# DXP.net
KiCad netlist of a schematic drawn in Altium Designer
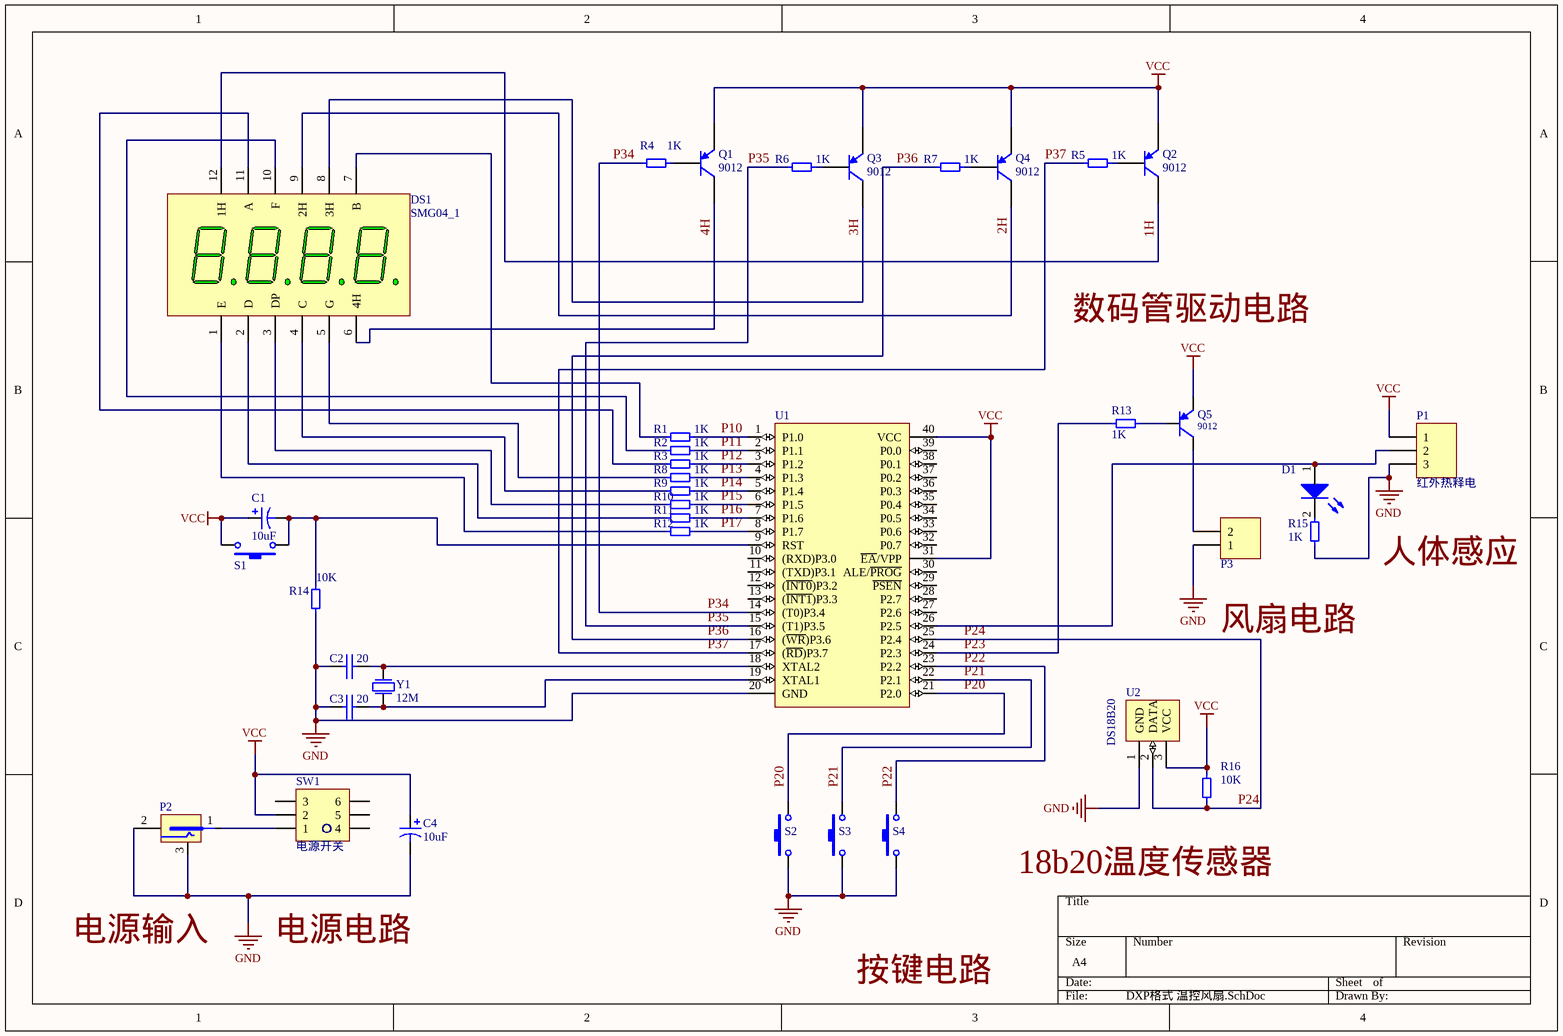
[diagram p0: DXP格式 温控风扇.SchDoc]

(export (version "E")
  (design (tool "Eeschema 10.0.6"))
  (components
    (comp (ref "C1")
      (value "10uF")
      (footprint "C_10")
      (description "Polarized Capacitor (Radial)")
      (fields (field (name "PUBLISHER") "Altium Limited"))
      (libsource (lib "简易动环监控系统") (part "Cap Pol1"))
    )
    (comp (ref "C2")
      (value "20")
      (footprint "CAP CP")
      (description "电容")
      (libsource (lib "C8051F020最小2") (part "CAP"))
    )
    (comp (ref "C3")
      (value "20")
      (footprint "CAP CP")
      (description "电容")
      (libsource (lib "C8051F020最小2") (part "CAP"))
    )
    (comp (ref "C4")
      (value "10uF")
      (footprint "C_10")
      (description "Polarized Capacitor (Radial)")
      (fields (field (name "PUBLISHER") "Altium Limited"))
      (libsource (lib "简易动环监控系统") (part "Cap Pol1"))
    )
    (comp (ref "D1") (value "~") (footprint "LED直插") (libsource (lib "实用原理图库") (part "D")))
    (comp (ref "DS1") (value "SMG04_1") (footprint "SMG04") (libsource (lib "我自己的") (part "SMG04_1")))
    (comp (ref "P1")
      (value "红外热释电")
      (footprint "HDR1X3")
      (description "Header, 3-Pin")
      (fields (field (name "PUBLISHER") "Altium Limited"))
      (libsource (lib "Miscellaneous Connectors") (part "MHDR1X3"))
    )
    (comp (ref "P2") (value "电源输入") (footprint "DC2.1") (libsource (lib "我自己的") (part "POWER")))
    (comp (ref "P3")
      (value "Header 2")
      (footprint "POWER -  小电源座")
      (description "Header, 2-Pin")
      (fields (field (name "PUBLISHER") "Altium Limited"))
      (libsource (lib "Miscellaneous Connectors") (part "Header 2"))
    )
    (comp (ref "Q1")
      (value "9012")
      (footprint "s三极管直插")
      (description "PNP General Purpose Amplifier")
      (fields (field (name "PUBLISHER") "Altium Limited"))
      (libsource (lib "Miscellaneous Devices") (part "2N3906"))
    )
    (comp (ref "Q2")
      (value "9012")
      (footprint "s三极管直插")
      (description "PNP General Purpose Amplifier")
      (fields (field (name "PUBLISHER") "Altium Limited"))
      (libsource (lib "Miscellaneous Devices") (part "2N3906"))
    )
    (comp (ref "Q3")
      (value "9012")
      (footprint "s三极管直插")
      (description "PNP General Purpose Amplifier")
      (fields (field (name "PUBLISHER") "Altium Limited"))
      (libsource (lib "Miscellaneous Devices") (part "2N3906"))
    )
    (comp (ref "Q4")
      (value "9012")
      (footprint "s三极管直插")
      (description "PNP General Purpose Amplifier")
      (fields (field (name "PUBLISHER") "Altium Limited"))
      (libsource (lib "Miscellaneous Devices") (part "2N3906"))
    )
    (comp (ref "Q5")
      (value "9012")
      (footprint "s三极管直插")
      (description "PNP General Purpose Amplifier")
      (fields (field (name "PUBLISHER") "Altium Limited"))
      (libsource (lib "实验板原理图") (part "2N3906"))
    )
    (comp (ref "R1") (value "1K") (footprint "AXIAL0.3") (libsource (lib "C8051F020最小2") (part "RES2")))
    (comp (ref "R2") (value "1K") (footprint "AXIAL0.3") (libsource (lib "C8051F020最小2") (part "RES2")))
    (comp (ref "R3") (value "1K") (footprint "AXIAL0.3") (libsource (lib "C8051F020最小2") (part "RES2")))
    (comp (ref "R4") (value "1K") (footprint "AXIAL0.3") (libsource (lib "C8051F020最小2") (part "RES2")))
    (comp (ref "R5") (value "1K") (footprint "AXIAL0.3") (libsource (lib "C8051F020最小2") (part "RES2")))
    (comp (ref "R6") (value "1K") (footprint "AXIAL0.3") (libsource (lib "C8051F020最小2") (part "RES2")))
    (comp (ref "R7") (value "1K") (footprint "AXIAL0.3") (libsource (lib "C8051F020最小2") (part "RES2")))
    (comp (ref "R8") (value "1K") (footprint "AXIAL0.3") (libsource (lib "C8051F020最小2") (part "RES2")))
    (comp (ref "R9") (value "1K") (footprint "AXIAL0.3") (libsource (lib "C8051F020最小2") (part "RES2")))
    (comp (ref "R10") (value "1K") (footprint "AXIAL0.3") (libsource (lib "C8051F020最小2") (part "RES2")))
    (comp (ref "R11") (value "1K") (footprint "AXIAL0.3") (libsource (lib "C8051F020最小2") (part "RES2")))
    (comp (ref "R12") (value "1K") (footprint "AXIAL0.3") (libsource (lib "C8051F020最小2") (part "RES2")))
    (comp (ref "R13") (value "1K") (footprint "res400mil") (libsource (lib "C8051F020最小2") (part "RES2")))
    (comp (ref "R14") (value "10K") (footprint "AXIAL0.3") (libsource (lib "C8051F020最小2") (part "RES2")))
    (comp (ref "R15") (value "1K") (footprint "AXIAL0.3") (libsource (lib "C8051F020最小2") (part "RES2")))
    (comp (ref "R16") (value "10K") (footprint "AXIAL0.3") (libsource (lib "C8051F020最小2") (part "RES2")))
    (comp (ref "S1")
      (value "SW-PB")
      (footprint "key")
      (description "Switch")
      (fields (field (name "PUBLISHER") "Altium Limited"))
      (libsource (lib "实验板原理图") (part "SW-PB"))
    )
    (comp (ref "S2")
      (value "SW-PB")
      (footprint "key")
      (description "Switch")
      (fields (field (name "PUBLISHER") "Altium Limited"))
      (libsource (lib "实验板原理图") (part "SW-PB"))
    )
    (comp (ref "S3")
      (value "SW-PB")
      (footprint "key")
      (description "Switch")
      (fields (field (name "PUBLISHER") "Altium Limited"))
      (libsource (lib "实验板原理图") (part "SW-PB"))
    )
    (comp (ref "S4")
      (value "SW-PB")
      (footprint "key")
      (description "Switch")
      (fields (field (name "PUBLISHER") "Altium Limited"))
      (libsource (lib "实验板原理图") (part "SW-PB"))
    )
    (comp (ref "SW1") (value "电源开关") (footprint "sw_自锁 1") (libsource (lib "我自己的") (part "SW1")))
    (comp (ref "U1") (value "STC89C52") (footprint "DIP40 - 做板") (libsource (lib "实验板原理图") (part "U1")))
    (comp (ref "U2") (value "DS18B20") (footprint "DS18B20") (libsource (lib "实验板原理图") (part "DS18B20")))
    (comp (ref "Y1")
      (value "12M")
      (footprint "XTAL")
      (description "Crystal Oscillator")
      (libsource (lib "C8051F020最小2") (part "16M"))
    )
  )
  (nets
    (net (code "1") (name "/1H") (class "Default")
      (node (ref "DS1") (pin "12") (pinfunction "1H_12") (pintype "passive"))
      (node (ref "Q2") (pin "3") (pinfunction "C_3") (pintype "passive"))
    )
    (net (code "2") (name "/2H") (class "Default")
      (node (ref "DS1") (pin "9") (pinfunction "2H_9") (pintype "passive"))
      (node (ref "Q4") (pin "3") (pinfunction "C_3") (pintype "passive"))
    )
    (net (code "3") (name "/3H") (class "Default")
      (node (ref "DS1") (pin "8") (pinfunction "3H_8") (pintype "passive"))
      (node (ref "Q3") (pin "3") (pinfunction "C_3") (pintype "passive"))
    )
    (net (code "4") (name "/4H") (class "Default")
      (node (ref "DS1") (pin "6") (pinfunction "4H_6") (pintype "passive"))
      (node (ref "Q1") (pin "3") (pinfunction "C_3") (pintype "passive"))
    )
    (net (code "6") (name "/P10") (class "Default")
      (node (ref "R1") (pin "1") (pinfunction "1_1") (pintype "passive"))
      (node (ref "U1") (pin "1") (pinfunction "P1.0_1") (pintype "bidirectional"))
    )
    (net (code "7") (name "/P11") (class "Default")
      (node (ref "R2") (pin "1") (pinfunction "1_1") (pintype "passive"))
      (node (ref "U1") (pin "2") (pinfunction "P1.1_2") (pintype "bidirectional"))
    )
    (net (code "8") (name "/P12") (class "Default")
      (node (ref "R3") (pin "1") (pinfunction "1_1") (pintype "passive"))
      (node (ref "U1") (pin "3") (pinfunction "P1.2_3") (pintype "bidirectional"))
    )
    (net (code "9") (name "/P13") (class "Default")
      (node (ref "R8") (pin "1") (pinfunction "1_1") (pintype "passive"))
      (node (ref "U1") (pin "4") (pinfunction "P1.3_4") (pintype "bidirectional"))
    )
    (net (code "10") (name "/P14") (class "Default")
      (node (ref "R9") (pin "1") (pinfunction "1_1") (pintype "passive"))
      (node (ref "U1") (pin "5") (pinfunction "P1.4_5") (pintype "bidirectional"))
    )
    (net (code "11") (name "/P15") (class "Default")
      (node (ref "R10") (pin "1") (pinfunction "1_1") (pintype "passive"))
      (node (ref "U1") (pin "6") (pinfunction "P1.5_6") (pintype "bidirectional"))
    )
    (net (code "12") (name "/P16") (class "Default")
      (node (ref "R11") (pin "1") (pinfunction "1_1") (pintype "passive"))
      (node (ref "U1") (pin "7") (pinfunction "P1.6_7") (pintype "bidirectional"))
    )
    (net (code "13") (name "/P17") (class "Default")
      (node (ref "R12") (pin "1") (pinfunction "1_1") (pintype "passive"))
      (node (ref "U1") (pin "8") (pinfunction "P1.7_8") (pintype "bidirectional"))
    )
    (net (code "14") (name "/P20") (class "Default")
      (node (ref "S2") (pin "2") (pinfunction "2_2") (pintype "passive"))
      (node (ref "U1") (pin "21") (pinfunction "P2.0_21") (pintype "bidirectional"))
    )
    (net (code "15") (name "/P21") (class "Default")
      (node (ref "S3") (pin "2") (pinfunction "2_2") (pintype "passive"))
      (node (ref "U1") (pin "22") (pinfunction "P2.1_22") (pintype "bidirectional"))
    )
    (net (code "16") (name "/P22") (class "Default")
      (node (ref "S4") (pin "2") (pinfunction "2_2") (pintype "passive"))
      (node (ref "U1") (pin "23") (pinfunction "P2.2_23") (pintype "bidirectional"))
    )
    (net (code "17") (name "/P23") (class "Default")
      (node (ref "R13") (pin "1") (pinfunction "1_1") (pintype "passive"))
      (node (ref "U1") (pin "24") (pinfunction "P2.3_24") (pintype "bidirectional"))
    )
    (net (code "18") (name "/P24") (class "Default")
      (node (ref "R16") (pin "1") (pinfunction "1_1") (pintype "passive"))
      (node (ref "U1") (pin "25") (pinfunction "P2.4_25") (pintype "bidirectional"))
      (node (ref "U2") (pin "2") (pinfunction "DATA_2") (pintype "bidirectional"))
    )
    (net (code "19") (name "/P34") (class "Default")
      (node (ref "R4") (pin "2") (pinfunction "2_2") (pintype "passive"))
      (node (ref "U1") (pin "14") (pinfunction "(T0)P3.4_14") (pintype "bidirectional"))
    )
    (net (code "20") (name "/P35") (class "Default")
      (node (ref "R6") (pin "2") (pinfunction "2_2") (pintype "passive"))
      (node (ref "U1") (pin "15") (pinfunction "(T1)P3.5_15") (pintype "bidirectional"))
    )
    (net (code "21") (name "/P36") (class "Default")
      (node (ref "R7") (pin "2") (pinfunction "2_2") (pintype "passive"))
      (node (ref "U1") (pin "16") (pinfunction "(~{WR})P3.6_16") (pintype "bidirectional"))
    )
    (net (code "22") (name "/P37") (class "Default")
      (node (ref "R5") (pin "2") (pinfunction "2_2") (pintype "passive"))
      (node (ref "U1") (pin "17") (pinfunction "(~{RD})P3.7_17") (pintype "bidirectional"))
    )
    (net (code "28") (name "GND") (class "Default")
      (node (ref "C2") (pin "1") (pinfunction "1_1") (pintype "passive"))
      (node (ref "C3") (pin "1") (pinfunction "1_1") (pintype "passive"))
      (node (ref "C4") (pin "2") (pinfunction "2_2") (pintype "passive"))
      (node (ref "P1") (pin "3") (pinfunction "3_3") (pintype "passive"))
      (node (ref "P2") (pin "2") (pintype "passive"))
      (node (ref "P2") (pin "3") (pintype "passive"))
      (node (ref "P3") (pin "1") (pinfunction "1_1") (pintype "passive"))
      (node (ref "R14") (pin "1") (pinfunction "1_1") (pintype "passive"))
      (node (ref "R15") (pin "1") (pinfunction "1_1") (pintype "passive"))
      (node (ref "S2") (pin "1") (pinfunction "1_1") (pintype "passive"))
      (node (ref "S3") (pin "1") (pinfunction "1_1") (pintype "passive"))
      (node (ref "S4") (pin "1") (pinfunction "1_1") (pintype "passive"))
      (node (ref "U1") (pin "20") (pinfunction "GND_20") (pintype "power_in"))
      (node (ref "U2") (pin "1") (pinfunction "GND_1") (pintype "power_in"))
    )
    (net (code "29") (name "Net-(D1-Pad2)") (class "Default")
      (node (ref "D1") (pin "2") (pintype "passive"))
      (node (ref "R15") (pin "2") (pinfunction "2_2") (pintype "passive"))
    )
    (net (code "30") (name "Net-(DS1-A)") (class "Default")
      (node (ref "DS1") (pin "11") (pinfunction "A_11") (pintype "passive"))
      (node (ref "R3") (pin "2") (pinfunction "2_2") (pintype "passive"))
    )
    (net (code "31") (name "Net-(DS1-B)") (class "Default")
      (node (ref "DS1") (pin "7") (pinfunction "B_7") (pintype "passive"))
      (node (ref "R1") (pin "2") (pinfunction "2_2") (pintype "passive"))
    )
    (net (code "32") (name "Net-(DS1-C)") (class "Default")
      (node (ref "DS1") (pin "4") (pinfunction "C_4") (pintype "passive"))
      (node (ref "R9") (pin "2") (pinfunction "2_2") (pintype "passive"))
    )
    (net (code "33") (name "Net-(DS1-D)") (class "Default")
      (node (ref "DS1") (pin "2") (pinfunction "D_2") (pintype "passive"))
      (node (ref "R11") (pin "2") (pinfunction "2_2") (pintype "passive"))
    )
    (net (code "34") (name "Net-(DS1-DP)") (class "Default")
      (node (ref "DS1") (pin "3") (pinfunction "DP_3") (pintype "passive"))
      (node (ref "R10") (pin "2") (pinfunction "2_2") (pintype "passive"))
    )
    (net (code "35") (name "Net-(DS1-E)") (class "Default")
      (node (ref "DS1") (pin "1") (pinfunction "E_1") (pintype "passive"))
      (node (ref "R12") (pin "2") (pinfunction "2_2") (pintype "passive"))
    )
    (net (code "36") (name "Net-(DS1-F)") (class "Default")
      (node (ref "DS1") (pin "10") (pinfunction "F_10") (pintype "passive"))
      (node (ref "R2") (pin "2") (pinfunction "2_2") (pintype "passive"))
    )
    (net (code "37") (name "Net-(DS1-G)") (class "Default")
      (node (ref "DS1") (pin "5") (pinfunction "G_5") (pintype "passive"))
      (node (ref "R8") (pin "2") (pinfunction "2_2") (pintype "passive"))
    )
    (net (code "38") (name "Net-(P2-Pad1)") (class "Default")
      (node (ref "P2") (pin "1") (pintype "passive"))
      (node (ref "SW1") (pin "1") (pinfunction "1_1") (pintype "passive"))
    )
    (net (code "39") (name "Net-(Q1-B)") (class "Default")
      (node (ref "Q1") (pin "2") (pinfunction "B_2") (pintype "passive"))
      (node (ref "R4") (pin "1") (pinfunction "1_1") (pintype "passive"))
    )
    (net (code "40") (name "Net-(Q2-B)") (class "Default")
      (node (ref "Q2") (pin "2") (pinfunction "B_2") (pintype "passive"))
      (node (ref "R5") (pin "1") (pinfunction "1_1") (pintype "passive"))
    )
    (net (code "41") (name "Net-(Q3-B)") (class "Default")
      (node (ref "Q3") (pin "2") (pinfunction "B_2") (pintype "passive"))
      (node (ref "R6") (pin "1") (pinfunction "1_1") (pintype "passive"))
    )
    (net (code "42") (name "Net-(Q4-B)") (class "Default")
      (node (ref "Q4") (pin "2") (pinfunction "B_2") (pintype "passive"))
      (node (ref "R7") (pin "1") (pinfunction "1_1") (pintype "passive"))
    )
    (net (code "43") (name "Net-(Q5-B)") (class "Default")
      (node (ref "Q5") (pin "2") (pinfunction "B_2") (pintype "passive"))
      (node (ref "R13") (pin "2") (pinfunction "2_2") (pintype "passive"))
    )
    (net (code "44") (name "Net-(Q5-C)") (class "Default")
      (node (ref "P3") (pin "2") (pinfunction "2_2") (pintype "passive"))
      (node (ref "Q5") (pin "3") (pinfunction "C_3") (pintype "passive"))
    )
    (net (code "45") (name "Net-(U1-P2.5)") (class "Default")
      (node (ref "D1") (pin "1") (pintype "passive"))
      (node (ref "P1") (pin "2") (pinfunction "2_2") (pintype "passive"))
      (node (ref "U1") (pin "26") (pinfunction "P2.5_26") (pintype "bidirectional"))
    )
    (net (code "46") (name "Net-(U1-RST)") (class "Default")
      (node (ref "C1") (pin "2") (pinfunction "2_2") (pintype "passive"))
      (node (ref "R14") (pin "2") (pinfunction "2_2") (pintype "passive"))
      (node (ref "S1") (pin "1") (pinfunction "1_1") (pintype "passive"))
      (node (ref "U1") (pin "9") (pinfunction "RST_9") (pintype "bidirectional"))
    )
    (net (code "47") (name "Net-(U1-XTAL1)") (class "Default")
      (node (ref "C3") (pin "2") (pinfunction "2_2") (pintype "passive"))
      (node (ref "U1") (pin "19") (pinfunction "XTAL1_19") (pintype "bidirectional"))
      (node (ref "Y1") (pin "2") (pinfunction "P2_2") (pintype "passive"))
    )
    (net (code "48") (name "Net-(U1-XTAL2)") (class "Default")
      (node (ref "C2") (pin "2") (pinfunction "2_2") (pintype "passive"))
      (node (ref "U1") (pin "18") (pinfunction "XTAL2_18") (pintype "bidirectional"))
      (node (ref "Y1") (pin "1") (pinfunction "P1_1") (pintype "passive"))
    )
    (net (code "49") (name "VCC") (class "Default")
      (node (ref "C1") (pin "1") (pinfunction "1_1") (pintype "passive"))
      (node (ref "C4") (pin "1") (pinfunction "1_1") (pintype "passive"))
      (node (ref "P1") (pin "1") (pinfunction "1_1") (pintype "passive"))
      (node (ref "Q1") (pin "1") (pinfunction "E_1") (pintype "passive"))
      (node (ref "Q2") (pin "1") (pinfunction "E_1") (pintype "passive"))
      (node (ref "Q3") (pin "1") (pinfunction "E_1") (pintype "passive"))
      (node (ref "Q4") (pin "1") (pinfunction "E_1") (pintype "passive"))
      (node (ref "Q5") (pin "1") (pinfunction "E_1") (pintype "passive"))
      (node (ref "R16") (pin "2") (pinfunction "2_2") (pintype "passive"))
      (node (ref "S1") (pin "2") (pinfunction "2_2") (pintype "passive"))
      (node (ref "SW1") (pin "2") (pinfunction "2_2") (pintype "passive"))
      (node (ref "U1") (pin "31") (pinfunction "~{EA}/VPP_31") (pintype "power_in"))
      (node (ref "U1") (pin "40") (pinfunction "VCC_40") (pintype "power_in"))
      (node (ref "U2") (pin "3") (pinfunction "VCC_3") (pintype "power_in"))
    )
    (net (code "50") (name "unconnected-(SW1-Pad3)") (class "Default")
      (node (ref "SW1") (pin "3") (pinfunction "3_3") (pintype "passive"))
    )
    (net (code "51") (name "unconnected-(SW1-Pad4)") (class "Default")
      (node (ref "SW1") (pin "4") (pinfunction "4_4") (pintype "passive"))
    )
    (net (code "52") (name "unconnected-(SW1-Pad5)") (class "Default")
      (node (ref "SW1") (pin "5") (pinfunction "5_5") (pintype "passive"))
    )
    (net (code "53") (name "unconnected-(SW1-Pad6)") (class "Default")
      (node (ref "SW1") (pin "6") (pinfunction "6_6") (pintype "passive"))
    )
    (net (code "54") (name "unconnected-(U1-(RXD)P3.0-Pad10)") (class "Default")
      (node (ref "U1") (pin "10") (pinfunction "(RXD)P3.0_10") (pintype "bidirectional"))
    )
    (net (code "55") (name "unconnected-(U1-(TXD)P3.1-Pad11)") (class "Default")
      (node (ref "U1") (pin "11") (pinfunction "(TXD)P3.1_11") (pintype "bidirectional"))
    )
    (net (code "56") (name "unconnected-(U1-(~{INT0})P3.2-Pad12)") (class "Default")
      (node (ref "U1") (pin "12") (pinfunction "(~{INT0})P3.2_12") (pintype "bidirectional"))
    )
    (net (code "57") (name "unconnected-(U1-(~{INT1})P3.3-Pad13)") (class "Default")
      (node (ref "U1") (pin "13") (pinfunction "(~{INT1})P3.3_13") (pintype "bidirectional"))
    )
    (net (code "58") (name "unconnected-(U1-ALE{slash}~{PROG}-Pad30)") (class "Default")
      (node (ref "U1") (pin "30") (pinfunction "ALE/~{PROG}_30") (pintype "bidirectional"))
    )
    (net (code "59") (name "unconnected-(U1-P0.0-Pad39)") (class "Default")
      (node (ref "U1") (pin "39") (pinfunction "P0.0_39") (pintype "bidirectional"))
    )
    (net (code "60") (name "unconnected-(U1-P0.1-Pad38)") (class "Default")
      (node (ref "U1") (pin "38") (pinfunction "P0.1_38") (pintype "bidirectional"))
    )
    (net (code "61") (name "unconnected-(U1-P0.2-Pad37)") (class "Default")
      (node (ref "U1") (pin "37") (pinfunction "P0.2_37") (pintype "bidirectional"))
    )
    (net (code "62") (name "unconnected-(U1-P0.3-Pad36)") (class "Default")
      (node (ref "U1") (pin "36") (pinfunction "P0.3_36") (pintype "bidirectional"))
    )
    (net (code "63") (name "unconnected-(U1-P0.4-Pad35)") (class "Default")
      (node (ref "U1") (pin "35") (pinfunction "P0.4_35") (pintype "bidirectional"))
    )
    (net (code "64") (name "unconnected-(U1-P0.5-Pad34)") (class "Default")
      (node (ref "U1") (pin "34") (pinfunction "P0.5_34") (pintype "bidirectional"))
    )
    (net (code "65") (name "unconnected-(U1-P0.6-Pad33)") (class "Default")
      (node (ref "U1") (pin "33") (pinfunction "P0.6_33") (pintype "bidirectional"))
    )
    (net (code "66") (name "unconnected-(U1-P0.7-Pad32)") (class "Default")
      (node (ref "U1") (pin "32") (pinfunction "P0.7_32") (pintype "bidirectional"))
    )
    (net (code "67") (name "unconnected-(U1-P2.6-Pad27)") (class "Default")
      (node (ref "U1") (pin "27") (pinfunction "P2.6_27") (pintype "bidirectional"))
    )
    (net (code "68") (name "unconnected-(U1-P2.7-Pad28)") (class "Default")
      (node (ref "U1") (pin "28") (pinfunction "P2.7_28") (pintype "bidirectional"))
    )
    (net (code "69") (name "unconnected-(U1-~{PSEN}-Pad29)") (class "Default")
      (node (ref "U1") (pin "29") (pinfunction "~{PSEN}_29") (pintype "bidirectional"))
    )
  )
)
